# Sheet_1_2020-07-27_09-10-31.net
KiCad netlist of a schematic drawn in Altium Designer
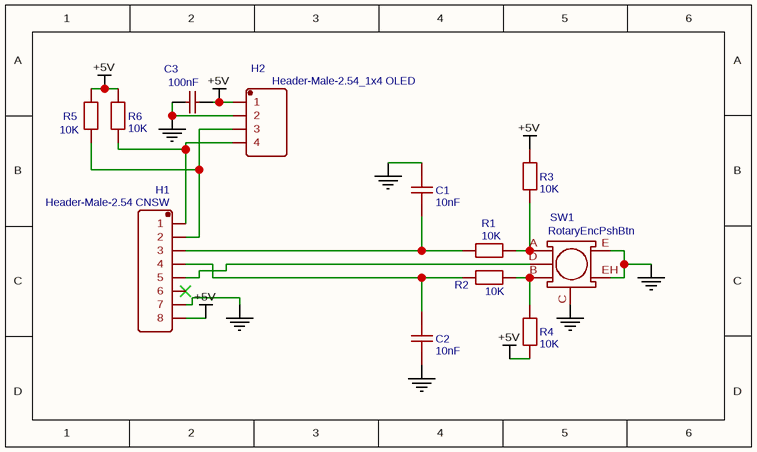
[diagram p0: Sheet_1_2020-07-27_09-10-31.schdoc]

(export (version "E")
  (design (tool "Eeschema 10.0.6"))
  (components
    (comp (ref "C1")
      (value "10nF")
      (fields
        (field (name "BOM_SUPPLIER PART") "C254082")
        (field (name "BOM_MANUFACTURER PART") "CC1H103ZA1AD3F4D10MF")
        (field (name "CONTRIBUTOR") "LCSC")
      )
      (libsource (lib "altium-import") (part "root_0_10nF_"))
    )
    (comp (ref "C2")
      (value "10nF")
      (fields
        (field (name "BOM_SUPPLIER PART") "C254082")
        (field (name "BOM_MANUFACTURER PART") "CC1H103ZA1AD3F4D10MF")
        (field (name "CONTRIBUTOR") "LCSC")
      )
      (libsource (lib "altium-import") (part "root_0_10nF_"))
    )
    (comp (ref "C3")
      (value "100nF")
      (fields
        (field (name "BOM_MANUFACTURER PART") "CS1F5.6Y5V1A104Z")
        (field (name "BOM_SUPPLIER PART") "C9306")
      )
      (libsource (lib "altium-import") (part "root_0_100nF_"))
    )
    (comp (ref "H1")
      (value "Header-Male-2.54 CNSW")
      (fields
        (field (name "BOM_MANUFACTURER PART") "210S-1*8P L=11.6MMGold-plated black")
        (field (name "BOM_SUPPLIER PART") "C124381")
        (field (name "CONTRIBUTOR") "LCSC")
      )
      (libsource (lib "altium-import") (part "root_0_Header-Male-2.54 CNSW_"))
    )
    (comp (ref "H2")
      (value "Header-Male-2.54_1x4 OLED")
      (fields
        (field (name "BOM_MANUFACTURER PART") "210S-1*4P L=11.6MMGold-plated black")
        (field (name "BOM_SUPPLIER PART") "C124378")
        (field (name "CONTRIBUTOR") "LCSC")
      )
      (libsource (lib "altium-import") (part "root_0_Header-Male-2.54_1x4 OLED_"))
    )
    (comp (ref "R1")
      (value "10K")
      (fields
        (field (name "BOM_SUPPLIER PART") "C410695")
        (field (name "BOM_MANUFACTURER PART") "RN 1/4W 10K F T/B A1")
        (field (name "CONTRIBUTOR") "LCSC")
      )
      (libsource (lib "altium-import") (part "root_0_10K_"))
    )
    (comp (ref "R2")
      (value "10K")
      (fields
        (field (name "BOM_SUPPLIER PART") "C410695")
        (field (name "BOM_MANUFACTURER PART") "RN 1/4W 10K F T/B A1")
        (field (name "CONTRIBUTOR") "LCSC")
      )
      (libsource (lib "altium-import") (part "root_0_10K_"))
    )
    (comp (ref "R3")
      (value "10K")
      (fields
        (field (name "BOM_SUPPLIER PART") "C410695")
        (field (name "BOM_MANUFACTURER PART") "RN 1/4W 10K F T/B A1")
        (field (name "CONTRIBUTOR") "LCSC")
      )
      (libsource (lib "altium-import") (part "root_1_10K_"))
    )
    (comp (ref "R4")
      (value "10K")
      (fields
        (field (name "BOM_SUPPLIER PART") "C410695")
        (field (name "BOM_MANUFACTURER PART") "RN 1/4W 10K F T/B A1")
        (field (name "CONTRIBUTOR") "LCSC")
      )
      (libsource (lib "altium-import") (part "root_1_10K_"))
    )
    (comp (ref "R5")
      (value "10K")
      (fields
        (field (name "BOM_SUPPLIER PART") "C410695")
        (field (name "BOM_MANUFACTURER PART") "RN 1/4W 10K F T/B A1")
        (field (name "CONTRIBUTOR") "LCSC")
      )
      (libsource (lib "altium-import") (part "root_1_10K_"))
    )
    (comp (ref "R6")
      (value "10K")
      (fields
        (field (name "BOM_SUPPLIER PART") "C410695")
        (field (name "BOM_MANUFACTURER PART") "RN 1/4W 10K F T/B A1")
        (field (name "CONTRIBUTOR") "LCSC")
      )
      (libsource (lib "altium-import") (part "root_1_10K_"))
    )
    (comp (ref "SW1")
      (value "RotaryEncPshBtn")
      (fields
        (field (name "BOM_SUPPLIER PART") "C470719")
        (field (name "BOM_MANUFACTURER PART") "EC11G1560414")
        (field (name "CONTRIBUTOR") "LCSC")
      )
      (libsource (lib "altium-import") (part "root_1_RotaryEncPshBtn_"))
    )
  )
  (nets
    (net (code "1") (name "+5V") (class "Default")
      (node (ref "C3") (pin "2") (pinfunction "2_2") (pintype "passive"))
      (node (ref "H1") (pin "8") (pinfunction "8_8") (pintype "passive"))
      (node (ref "H2") (pin "1") (pinfunction "1_1") (pintype "passive"))
      (node (ref "R3") (pin "2") (pinfunction "2_2") (pintype "passive"))
      (node (ref "R4") (pin "1") (pinfunction "1_1") (pintype "passive"))
      (node (ref "R5") (pin "2") (pinfunction "2_2") (pintype "passive"))
      (node (ref "R6") (pin "2") (pinfunction "2_2") (pintype "passive"))
    )
    (net (code "2") (name "GND") (class "Default")
      (node (ref "C1") (pin "2") (pinfunction "2_2") (pintype "passive"))
      (node (ref "C2") (pin "1") (pinfunction "1_1") (pintype "passive"))
      (node (ref "C3") (pin "1") (pinfunction "1_1") (pintype "passive"))
      (node (ref "H1") (pin "7") (pinfunction "7_7") (pintype "passive"))
      (node (ref "H2") (pin "2") (pinfunction "2_2") (pintype "passive"))
      (node (ref "SW1") (pin "C") (pinfunction "C_C") (pintype "passive"))
      (node (ref "SW1") (pin "E") (pinfunction "E_E") (pintype "passive"))
      (node (ref "SW1") (pin "EH") (pinfunction "EH_EH") (pintype "passive"))
    )
    (net (code "3") (name "Net-(C1-Pad1)") (class "Default")
      (node (ref "C1") (pin "1") (pinfunction "1_1") (pintype "passive"))
      (node (ref "H1") (pin "3") (pinfunction "3_3") (pintype "passive"))
      (node (ref "R1") (pin "1") (pinfunction "1_1") (pintype "passive"))
    )
    (net (code "4") (name "Net-(C2-Pad2)") (class "Default")
      (node (ref "C2") (pin "2") (pinfunction "2_2") (pintype "passive"))
      (node (ref "H1") (pin "4") (pinfunction "4_4") (pintype "passive"))
      (node (ref "R2") (pin "1") (pinfunction "1_1") (pintype "passive"))
    )
    (net (code "5") (name "Net-(H1-Pad1)") (class "Default")
      (node (ref "H1") (pin "1") (pinfunction "1_1") (pintype "passive"))
      (node (ref "H2") (pin "4") (pinfunction "4_4") (pintype "passive"))
      (node (ref "R6") (pin "1") (pinfunction "1_1") (pintype "passive"))
    )
    (net (code "6") (name "Net-(H1-Pad2)") (class "Default")
      (node (ref "H1") (pin "2") (pinfunction "2_2") (pintype "passive"))
      (node (ref "H2") (pin "3") (pinfunction "3_3") (pintype "passive"))
      (node (ref "R5") (pin "1") (pinfunction "1_1") (pintype "passive"))
    )
    (net (code "7") (name "Net-(H1-Pad5)") (class "Default")
      (node (ref "H1") (pin "5") (pinfunction "5_5") (pintype "passive"))
      (node (ref "SW1") (pin "D") (pinfunction "D_D") (pintype "passive"))
    )
    (net (code "8") (name "Net-(R1-Pad2)") (class "Default")
      (node (ref "R1") (pin "2") (pinfunction "2_2") (pintype "passive"))
      (node (ref "R3") (pin "1") (pinfunction "1_1") (pintype "passive"))
      (node (ref "SW1") (pin "A") (pinfunction "A_A") (pintype "passive"))
    )
    (net (code "9") (name "Net-(R2-Pad2)") (class "Default")
      (node (ref "R2") (pin "2") (pinfunction "2_2") (pintype "passive"))
      (node (ref "R4") (pin "2") (pinfunction "2_2") (pintype "passive"))
      (node (ref "SW1") (pin "B") (pinfunction "B_B") (pintype "passive"))
    )
    (net (code "10") (name "unconnected-(H1-Pad6)") (class "Default")
      (node (ref "H1") (pin "6") (pinfunction "6_6") (pintype "passive+no_connect"))
    )
  )
)
